# 2_MCU.net
KiCad netlist of a schematic drawn in Altium Designer
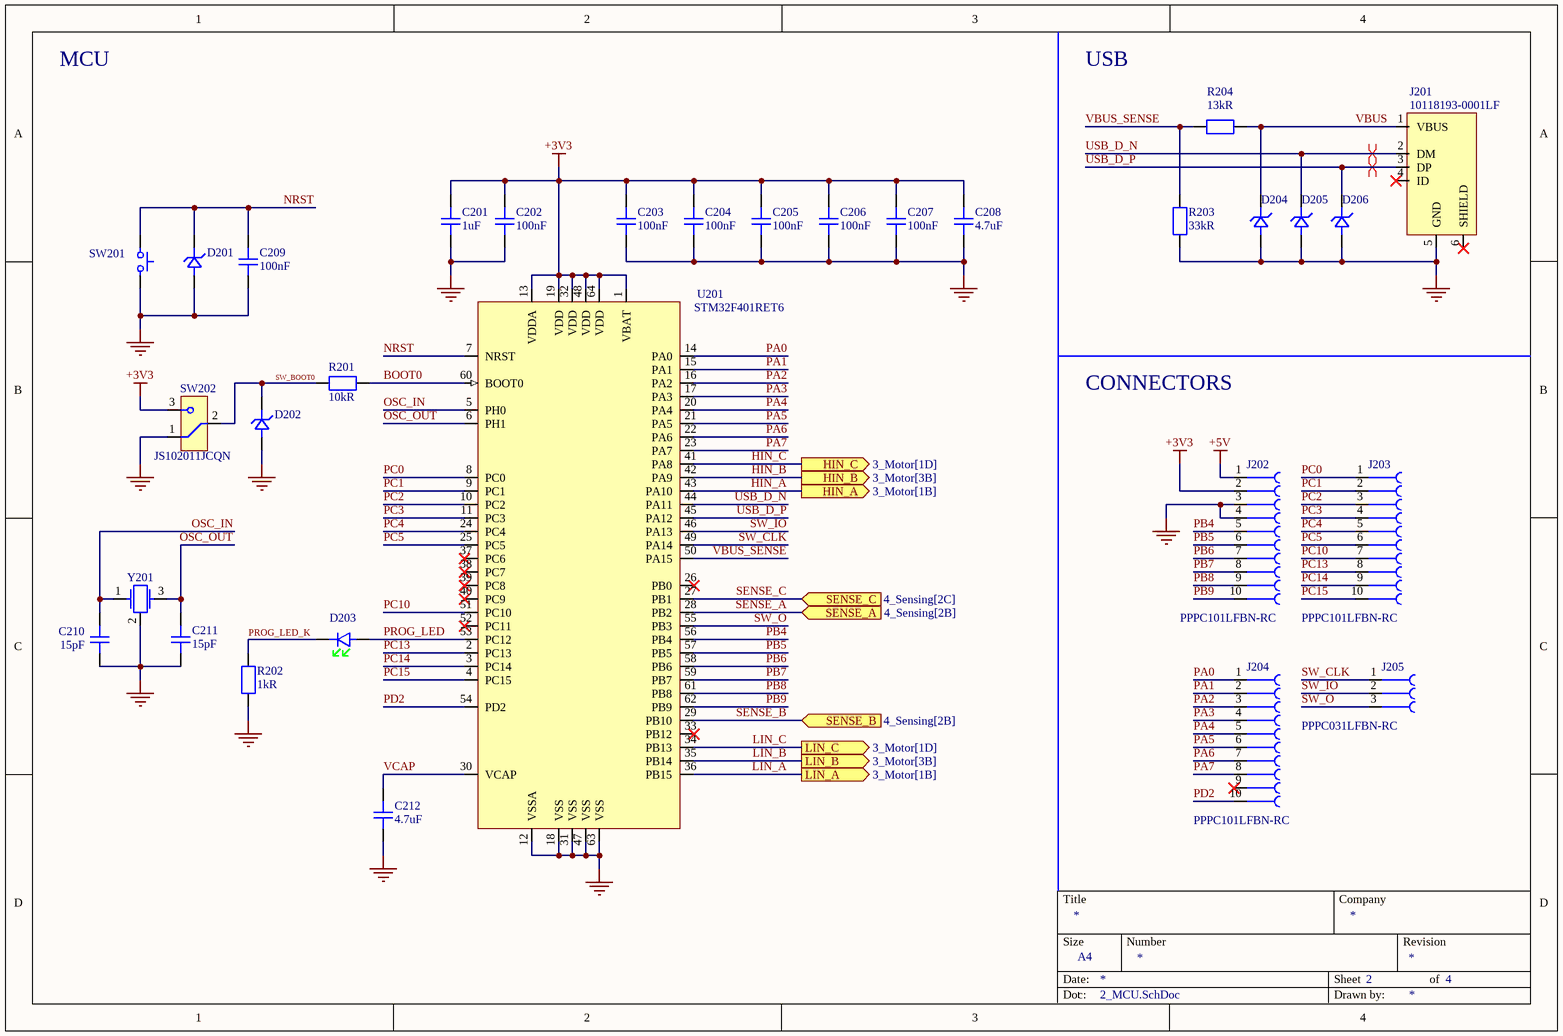
[diagram p0: 2_MCU.SchDoc]

(export (version "E")
  (design (tool "Eeschema 10.0.6"))
  (components
    (comp (ref "C201")
      (value "1uF")
      (footprint "C_Yageo_CC_0603_A")
      (description "Multilayer Ceramic Capacitor, 1 uF, 16 V, ± 10%, X7R, 0603 [1608 Metric]")
      (fields (field (name "TOLERANCE") "10%") (field (name "VOLTAGE") "16V"))
      (libsource (lib "Dennis Micro Computers") (part "C"))
    )
    (comp (ref "C202")
      (value "100nF")
      (footprint "C_Yageo_CC_0402_A")
      (description "Multilayer Ceramic Capacitor, 0.1 uF, 10 V, ± 20%, X7R, 0402 [1005 Metric]")
      (fields (field (name "TOLERANCE") "20%") (field (name "LCSC PART NUMBER") "C2171572"))
      (libsource (lib "Dennis Micro Computers") (part "C"))
    )
    (comp (ref "C203")
      (value "100nF")
      (footprint "C_Yageo_CC_0402_A")
      (description "Multilayer Ceramic Capacitor, 0.1 uF, 10 V, ± 20%, X7R, 0402 [1005 Metric]")
      (fields (field (name "TOLERANCE") "20%") (field (name "LCSC PART NUMBER") "C2171572"))
      (libsource (lib "Dennis Micro Computers") (part "C"))
    )
    (comp (ref "C204")
      (value "100nF")
      (footprint "C_Yageo_CC_0402_A")
      (description "Multilayer Ceramic Capacitor, 0.1 uF, 10 V, ± 20%, X7R, 0402 [1005 Metric]")
      (fields (field (name "TOLERANCE") "20%") (field (name "LCSC PART NUMBER") "C2171572"))
      (libsource (lib "Dennis Micro Computers") (part "C"))
    )
    (comp (ref "C205")
      (value "100nF")
      (footprint "C_Yageo_CC_0402_A")
      (description "Multilayer Ceramic Capacitor, 0.1 uF, 10 V, ± 20%, X7R, 0402 [1005 Metric]")
      (fields (field (name "TOLERANCE") "20%") (field (name "LCSC PART NUMBER") "C2171572"))
      (libsource (lib "Dennis Micro Computers") (part "C"))
    )
    (comp (ref "C206")
      (value "100nF")
      (footprint "C_Yageo_CC_0402_A")
      (description "Multilayer Ceramic Capacitor, 0.1 uF, 10 V, ± 20%, X7R, 0402 [1005 Metric]")
      (fields (field (name "TOLERANCE") "20%") (field (name "LCSC PART NUMBER") "C2171572"))
      (libsource (lib "Dennis Micro Computers") (part "C"))
    )
    (comp (ref "C207")
      (value "100nF")
      (footprint "C_Yageo_CC_0402_A")
      (description "Multilayer Ceramic Capacitor, 0.1 uF, 10 V, ± 20%, X7R, 0402 [1005 Metric]")
      (fields (field (name "TOLERANCE") "20%") (field (name "LCSC PART NUMBER") "C2171572"))
      (libsource (lib "Dennis Micro Computers") (part "C"))
    )
    (comp (ref "C208")
      (value "4.7uF")
      (footprint "C_Yageo_CC_0402_A")
      (description "Multilayer Ceramic Capacitor, 4.7 uF, 50 V, ± 10%, X5R, 0402 [1005 Metric]")
      (fields (field (name "TOLERANCE") "20%") (field (name "LCSC PART NUMBER") "C469468"))
      (libsource (lib "Dennis Micro Computers") (part "C"))
    )
    (comp (ref "C209")
      (value "100nF")
      (footprint "C_Yageo_CC_0402_A")
      (description "Multilayer Ceramic Capacitor, 0.1 uF, 10 V, ± 20%, X7R, 0402 [1005 Metric]")
      (fields (field (name "TOLERANCE") "20%") (field (name "LCSC PART NUMBER") "C2171572"))
      (libsource (lib "Dennis Micro Computers") (part "C"))
    )
    (comp (ref "C210")
      (value "15pF")
      (footprint "C_Yageo_CC_0402_A")
      (description "Multilayer Ceramic Capacitor, 15 pF, 10 V, ± 5%, X7R, 0402 [1005 Metric]")
      (fields (field (name "TOLERANCE") "5%") (field (name "VOLTAGE") "50V"))
      (libsource (lib "Dennis Micro Computers") (part "C"))
    )
    (comp (ref "C211")
      (value "15pF")
      (footprint "C_Yageo_CC_0402_A")
      (description "Multilayer Ceramic Capacitor, 15 pF, 10 V, ± 5%, X7R, 0402 [1005 Metric]")
      (fields (field (name "TOLERANCE") "5%") (field (name "VOLTAGE") "50V"))
      (libsource (lib "Dennis Micro Computers") (part "C"))
    )
    (comp (ref "C212")
      (value "4.7uF")
      (footprint "C_Yageo_CC_0402_A")
      (description "Multilayer Ceramic Capacitor, 4.7 uF, 50 V, ± 10%, X5R, 0402 [1005 Metric]")
      (fields (field (name "TOLERANCE") "20%") (field (name "LCSC PART NUMBER") "C469468"))
      (libsource (lib "Dennis Micro Computers") (part "C"))
    )
    (comp (ref "D201")
      (value "D5V0F1U2S9-7")
      (footprint "D_TVS_Uni_Diodes_SOD-923_B")
      (description "Diode TVS Dual Uni-Dir 5.5V 250000W 2-Pin SOD-923 T/R")
      (fields (field (name "LCSC PART NUMBER") "C508179"))
      (libsource (lib "Dennis Micro Computers") (part "D_TVS_Uni"))
    )
    (comp (ref "D202")
      (value "D5V0F1U2S9-7")
      (footprint "D_TVS_Uni_Diodes_SOD-923_B")
      (description "Diode TVS Dual Uni-Dir 5.5V 250000W 2-Pin SOD-923 T/R")
      (fields (field (name "LCSC PART NUMBER") "C508179"))
      (libsource (lib "Dennis Micro Computers") (part "D_TVS_Uni"))
    )
    (comp (ref "D203")
      (value "150080GS75000")
      (footprint "D_LED_We_150080GS75000")
      (description "WURTH ELEKTRONIK - 150080GS75000 - LED, Green, SMD, 0805, 30 mA, 3.2 V, 520 nm")
      (fields (field (name "LCSC PART NUMBER") "C2890404"))
      (libsource (lib "Dennis Micro Computers") (part "D_LED_Green"))
    )
    (comp (ref "D204")
      (value "D5V0F1U2S9-7")
      (footprint "D_TVS_Uni_Diodes_SOD-923_B")
      (description "Diode TVS Dual Uni-Dir 5.5V 250000W 2-Pin SOD-923 T/R")
      (fields (field (name "LCSC PART NUMBER") "C508179"))
      (libsource (lib "Dennis Micro Computers") (part "D_TVS_Uni"))
    )
    (comp (ref "D205")
      (value "D5V0F1U2S9-7")
      (footprint "D_TVS_Uni_Diodes_SOD-923_B")
      (description "Diode TVS Dual Uni-Dir 5.5V 250000W 2-Pin SOD-923 T/R")
      (fields (field (name "LCSC PART NUMBER") "C508179"))
      (libsource (lib "Dennis Micro Computers") (part "D_TVS_Uni"))
    )
    (comp (ref "D206")
      (value "D5V0F1U2S9-7")
      (footprint "D_TVS_Uni_Diodes_SOD-923_B")
      (description "Diode TVS Dual Uni-Dir 5.5V 250000W 2-Pin SOD-923 T/R")
      (fields (field (name "LCSC PART NUMBER") "C508179"))
      (libsource (lib "Dennis Micro Computers") (part "D_TVS_Uni"))
    )
    (comp (ref "J201")
      (value "10118193-0001LF")
      (footprint "J_USB_Micro-B_Amphenol_10118193-0001LF")
      (description "Usb Connector, 5 Contact(S), Female, Right Angle, Surface Mount Terminal, Locking, Receptacle")
      (fields (field (name "LCSC PART NUMBER") "C132562"))
      (libsource (lib "Dennis Micro Computers") (part "J_USB2_B_Micro"))
    )
    (comp (ref "J202")
      (value "PPPC101LFBN-RC")
      (footprint "J_Sullins_01x07_Socket_2.54mm")
      (description "10 Position Total Single Row 2.54 mm Pitch Straight Female Header")
      (fields (field (name "LCSC PART NUMBER") "Null"))
      (libsource (lib "Dennis Micro Computers") (part "J_01x10_Socket"))
    )
    (comp (ref "J203")
      (value "PPPC101LFBN-RC")
      (footprint "J_Sullins_01x07_Socket_2.54mm")
      (description "10 Position Total Single Row 2.54 mm Pitch Straight Female Header")
      (fields (field (name "LCSC PART NUMBER") "Null"))
      (libsource (lib "Dennis Micro Computers") (part "J_01x10_Socket"))
    )
    (comp (ref "J204")
      (value "PPPC101LFBN-RC")
      (footprint "J_Sullins_01x07_Socket_2.54mm")
      (description "10 Position Total Single Row 2.54 mm Pitch Straight Female Header")
      (fields (field (name "LCSC PART NUMBER") "Null"))
      (libsource (lib "Dennis Micro Computers") (part "J_01x10_Socket"))
    )
    (comp (ref "J205")
      (value "PPPC031LFBN-RC")
      (footprint "J_Sullins_01x03_Socket_2.54mm")
      (description "3 Position Total Single Row 2.54 mm Pitch Straight Female Header")
      (fields (field (name "LCSC PART NUMBER") "Null"))
      (libsource (lib "Dennis Micro Computers") (part "J_01x03_Socket"))
    )
    (comp (ref "R201")
      (value "10kR")
      (footprint "R_Yageo_RCL_0402_A")
      (description "SMD Chip Resistor, 10 kOhm, ± 1%, 62.5 mW, 0402 [1005 Metric], Thick Film, General Purpose")
      (fields (field (name "TOLERANCE") "1%") (field (name "LCSC PART NUMBER") "C60490"))
      (libsource (lib "Dennis Micro Computers") (part "R"))
    )
    (comp (ref "R202")
      (value "1kR")
      (footprint "R_Yageo_RCL_0402_A")
      (description "SMD Chip Resistor, 1 kOhm, ± 1%, 62.5 mW, 0402 [1005 Metric], Thick Film, General Purpose")
      (fields (field (name "TOLERANCE") "1%") (field (name "LCSC PART NUMBER") "C106235"))
      (libsource (lib "Dennis Micro Computers") (part "R"))
    )
    (comp (ref "R203")
      (value "33kR")
      (footprint "R_Yageo_RCL_0402_A")
      (description "SMD Chip Resistor, 33 kOhm, ± 1%, 63 mW, 0402 [1005 Metric], Thick Film, General Purpose")
      (fields (field (name "TOLERANCE") "1%") (field (name "LCSC PART NUMBER") "C138003"))
      (libsource (lib "Dennis Micro Computers") (part "R"))
    )
    (comp (ref "R204")
      (value "13kR")
      (footprint "R_Yageo_RCL_0402_A")
      (description "SMD Chip Resistor, 13 kOhm, ± 1%, 63 mW, 0402 [1005 Metric], Thick Film, General Purpose")
      (fields (field (name "TOLERANCE") "1%") (field (name "LCSC PART NUMBER") "C138057"))
      (libsource (lib "Dennis Micro Computers") (part "R"))
    )
    (comp (ref "SW201")
      (value "PTS647SN50SMTR2LFS")
      (footprint "SW_Tactitle_SPST_C&K_PTS647SN50SMTR2LFS")
      (description "Switch Tactile N.O. SPST Round Button Gull Wing 0.05A 12VDC 100000Cycles 0.98N SMD T/R")
      (fields (field (name "LCSC PART NUMBER") "C2799414"))
      (libsource (lib "Dennis Micro Computers") (part "SW_Tactile_SPST"))
    )
    (comp (ref "SW202")
      (value "JS102011JCQN")
      (footprint "SW_Slide_C&K_JS102011JCQN")
      (description "JS Series Sub-Miniature Slide Switch SPDT On-On Top Slide 0.3A 6VDC J-Lead Surface Mount T/R")
      (fields (field (name "LCSC PART NUMBER") "C221659"))
      (libsource (lib "Dennis Micro Computers") (part "SW_Slide_SPDT"))
    )
    (comp (ref "U201")
      (value "STM32F401RET6")
      (footprint "U_ST_STM32F401xD/xE_B")
      (description "MCU 32-bit STM32 ARM Cortex M4 RISC 512KB Flash 1.8V/2.5V/3.3V 64-Pin LQFP Tray")
      (fields (field (name "LCSC PART NUMBER") "C116978"))
      (libsource (lib "Dennis Micro Computers") (part "U_STM32F401xD/xE"))
    )
    (comp (ref "Y201")
      (value "ECS-240-12-37B-CKY-TR")
      (footprint "Y_Crystal_GND24_ECS_240-12-37B-CKY-TR")
      (description "Crystal 24MHz ±10ppm (Tol) ±10ppm (Stability) 12pF FUND 50Ohm 4-Pin Mini-CSMD T/R")
      (fields (field (name "LCSC PART NUMBER") "C2450025"))
      (libsource (lib "Dennis Micro Computers") (part "Y_Crystal_GND24"))
    )
  )
  (nets
    (net (code "1") (name "+3V3") (class "Default")
      (node (ref "C201") (pin "2") (pinfunction "2_2") (pintype "passive"))
      (node (ref "C202") (pin "2") (pinfunction "2_2") (pintype "passive"))
      (node (ref "C203") (pin "2") (pinfunction "2_2") (pintype "passive"))
      (node (ref "C204") (pin "2") (pinfunction "2_2") (pintype "passive"))
      (node (ref "C205") (pin "2") (pinfunction "2_2") (pintype "passive"))
      (node (ref "C206") (pin "2") (pinfunction "2_2") (pintype "passive"))
      (node (ref "C207") (pin "2") (pinfunction "2_2") (pintype "passive"))
      (node (ref "C208") (pin "2") (pinfunction "2_2") (pintype "passive"))
      (node (ref "J202") (pin "2") (pinfunction "2_2") (pintype "passive"))
      (node (ref "SW202") (pin "3") (pinfunction "3_3") (pintype "passive"))
      (node (ref "U201") (pin "1") (pinfunction "VBAT_1") (pintype "power_in"))
      (node (ref "U201") (pin "13") (pinfunction "VDDA_13") (pintype "power_in"))
      (node (ref "U201") (pin "19") (pinfunction "VDD_19") (pintype "power_in"))
      (node (ref "U201") (pin "32") (pinfunction "VDD_32") (pintype "power_in"))
      (node (ref "U201") (pin "48") (pinfunction "VDD_48") (pintype "power_in"))
      (node (ref "U201") (pin "64") (pinfunction "VDD_64") (pintype "power_in"))
    )
    (net (code "2") (name "+5V") (class "Default")
      (node (ref "J202") (pin "1") (pinfunction "1_1") (pintype "passive"))
    )
    (net (code "3") (name "/BOOT0") (class "Default")
      (node (ref "R201") (pin "2") (pinfunction "2_2") (pintype "passive"))
      (node (ref "U201") (pin "60") (pinfunction "BOOT0_60") (pintype "input"))
    )
    (net (code "4") (name "/HIN_A") (class "Default")
      (node (ref "U201") (pin "43") (pinfunction "PA10_43") (pintype "bidirectional"))
    )
    (net (code "5") (name "/HIN_B") (class "Default")
      (node (ref "U201") (pin "42") (pinfunction "PA9_42") (pintype "bidirectional"))
    )
    (net (code "6") (name "/HIN_C") (class "Default")
      (node (ref "U201") (pin "41") (pinfunction "PA8_41") (pintype "bidirectional"))
    )
    (net (code "7") (name "/LIN_A") (class "Default")
      (node (ref "U201") (pin "36") (pinfunction "PB15_36") (pintype "bidirectional"))
    )
    (net (code "8") (name "/LIN_B") (class "Default")
      (node (ref "U201") (pin "35") (pinfunction "PB14_35") (pintype "bidirectional"))
    )
    (net (code "9") (name "/LIN_C") (class "Default")
      (node (ref "U201") (pin "34") (pinfunction "PB13_34") (pintype "bidirectional"))
    )
    (net (code "10") (name "/NRST") (class "Default")
      (node (ref "C209") (pin "2") (pinfunction "2_2") (pintype "passive"))
      (node (ref "D201") (pin "1") (pinfunction "1_1") (pintype "passive"))
      (node (ref "SW201") (pin "1") (pinfunction "1_1") (pintype "passive"))
      (node (ref "U201") (pin "7") (pinfunction "NRST_7") (pintype "bidirectional"))
    )
    (net (code "11") (name "/OSC_IN") (class "Default")
      (node (ref "C210") (pin "2") (pinfunction "2_2") (pintype "passive"))
      (node (ref "U201") (pin "5") (pinfunction "PH0_5") (pintype "bidirectional"))
      (node (ref "Y201") (pin "1") (pinfunction "1_1") (pintype "passive"))
    )
    (net (code "12") (name "/OSC_OUT") (class "Default")
      (node (ref "C211") (pin "2") (pinfunction "2_2") (pintype "passive"))
      (node (ref "U201") (pin "6") (pinfunction "PH1_6") (pintype "bidirectional"))
      (node (ref "Y201") (pin "3") (pinfunction "3_3") (pintype "passive"))
    )
    (net (code "13") (name "/PA0") (class "Default")
      (node (ref "J204") (pin "1") (pinfunction "1_1") (pintype "passive"))
      (node (ref "U201") (pin "14") (pinfunction "PA0_14") (pintype "bidirectional"))
    )
    (net (code "14") (name "/PA1") (class "Default")
      (node (ref "J204") (pin "2") (pinfunction "2_2") (pintype "passive"))
      (node (ref "U201") (pin "15") (pinfunction "PA1_15") (pintype "bidirectional"))
    )
    (net (code "15") (name "/PA2") (class "Default")
      (node (ref "J204") (pin "3") (pinfunction "3_3") (pintype "passive"))
      (node (ref "U201") (pin "16") (pinfunction "PA2_16") (pintype "bidirectional"))
    )
    (net (code "16") (name "/PA3") (class "Default")
      (node (ref "J204") (pin "4") (pinfunction "4_4") (pintype "passive"))
      (node (ref "U201") (pin "17") (pinfunction "PA3_17") (pintype "bidirectional"))
    )
    (net (code "17") (name "/PA4") (class "Default")
      (node (ref "J204") (pin "5") (pinfunction "5_5") (pintype "passive"))
      (node (ref "U201") (pin "20") (pinfunction "PA4_20") (pintype "bidirectional"))
    )
    (net (code "18") (name "/PA5") (class "Default")
      (node (ref "J204") (pin "6") (pinfunction "6_6") (pintype "passive"))
      (node (ref "U201") (pin "21") (pinfunction "PA5_21") (pintype "bidirectional"))
    )
    (net (code "19") (name "/PA6") (class "Default")
      (node (ref "J204") (pin "7") (pinfunction "7_7") (pintype "passive"))
      (node (ref "U201") (pin "22") (pinfunction "PA6_22") (pintype "bidirectional"))
    )
    (net (code "20") (name "/PA7") (class "Default")
      (node (ref "J204") (pin "8") (pinfunction "8_8") (pintype "passive"))
      (node (ref "U201") (pin "23") (pinfunction "PA7_23") (pintype "bidirectional"))
    )
    (net (code "21") (name "/PB4") (class "Default")
      (node (ref "J202") (pin "5") (pinfunction "5_5") (pintype "passive"))
      (node (ref "U201") (pin "56") (pinfunction "PB4_56") (pintype "bidirectional"))
    )
    (net (code "22") (name "/PB5") (class "Default")
      (node (ref "J202") (pin "6") (pinfunction "6_6") (pintype "passive"))
      (node (ref "U201") (pin "57") (pinfunction "PB5_57") (pintype "bidirectional"))
    )
    (net (code "23") (name "/PB6") (class "Default")
      (node (ref "J202") (pin "7") (pinfunction "7_7") (pintype "passive"))
      (node (ref "U201") (pin "58") (pinfunction "PB6_58") (pintype "bidirectional"))
    )
    (net (code "24") (name "/PB7") (class "Default")
      (node (ref "J202") (pin "8") (pinfunction "8_8") (pintype "passive"))
      (node (ref "U201") (pin "59") (pinfunction "PB7_59") (pintype "bidirectional"))
    )
    (net (code "25") (name "/PB8") (class "Default")
      (node (ref "J202") (pin "9") (pinfunction "9_9") (pintype "passive"))
      (node (ref "U201") (pin "61") (pinfunction "PB8_61") (pintype "bidirectional"))
    )
    (net (code "26") (name "/PB9") (class "Default")
      (node (ref "J202") (pin "10") (pinfunction "10_10") (pintype "passive"))
      (node (ref "U201") (pin "62") (pinfunction "PB9_62") (pintype "bidirectional"))
    )
    (net (code "27") (name "/PC0") (class "Default")
      (node (ref "J203") (pin "1") (pinfunction "1_1") (pintype "passive"))
      (node (ref "U201") (pin "8") (pinfunction "PC0_8") (pintype "bidirectional"))
    )
    (net (code "28") (name "/PC1") (class "Default")
      (node (ref "J203") (pin "2") (pinfunction "2_2") (pintype "passive"))
      (node (ref "U201") (pin "9") (pinfunction "PC1_9") (pintype "bidirectional"))
    )
    (net (code "29") (name "/PC2") (class "Default")
      (node (ref "J203") (pin "3") (pinfunction "3_3") (pintype "passive"))
      (node (ref "U201") (pin "10") (pinfunction "PC2_10") (pintype "bidirectional"))
    )
    (net (code "30") (name "/PC3") (class "Default")
      (node (ref "J203") (pin "4") (pinfunction "4_4") (pintype "passive"))
      (node (ref "U201") (pin "11") (pinfunction "PC3_11") (pintype "bidirectional"))
    )
    (net (code "31") (name "/PC4") (class "Default")
      (node (ref "J203") (pin "5") (pinfunction "5_5") (pintype "passive"))
      (node (ref "U201") (pin "24") (pinfunction "PC4_24") (pintype "bidirectional"))
    )
    (net (code "32") (name "/PC5") (class "Default")
      (node (ref "J203") (pin "6") (pinfunction "6_6") (pintype "passive"))
      (node (ref "U201") (pin "25") (pinfunction "PC5_25") (pintype "bidirectional"))
    )
    (net (code "33") (name "/PC10") (class "Default")
      (node (ref "J203") (pin "7") (pinfunction "7_7") (pintype "passive"))
      (node (ref "U201") (pin "51") (pinfunction "PC10_51") (pintype "bidirectional"))
    )
    (net (code "34") (name "/PC13") (class "Default")
      (node (ref "J203") (pin "8") (pinfunction "8_8") (pintype "passive"))
      (node (ref "U201") (pin "2") (pinfunction "PC13_2") (pintype "bidirectional"))
    )
    (net (code "35") (name "/PC14") (class "Default")
      (node (ref "J203") (pin "9") (pinfunction "9_9") (pintype "passive"))
      (node (ref "U201") (pin "3") (pinfunction "PC14_3") (pintype "bidirectional"))
    )
    (net (code "36") (name "/PC15") (class "Default")
      (node (ref "J203") (pin "10") (pinfunction "10_10") (pintype "passive"))
      (node (ref "U201") (pin "4") (pinfunction "PC15_4") (pintype "bidirectional"))
    )
    (net (code "37") (name "/PD2") (class "Default")
      (node (ref "J204") (pin "10") (pinfunction "10_10") (pintype "passive"))
      (node (ref "U201") (pin "54") (pinfunction "PD2_54") (pintype "bidirectional"))
    )
    (net (code "38") (name "/PROG_LED") (class "Default")
      (node (ref "D203") (pin "1") (pinfunction "1_1") (pintype "passive"))
      (node (ref "U201") (pin "53") (pinfunction "PC12_53") (pintype "bidirectional"))
    )
    (net (code "39") (name "/PROG_LED_K") (class "Default")
      (node (ref "D203") (pin "2") (pinfunction "2_2") (pintype "passive"))
      (node (ref "R202") (pin "2") (pinfunction "2_2") (pintype "passive"))
    )
    (net (code "40") (name "/SENSE_A") (class "Default")
      (node (ref "U201") (pin "28") (pinfunction "PB2_28") (pintype "bidirectional"))
    )
    (net (code "41") (name "/SENSE_B") (class "Default")
      (node (ref "U201") (pin "29") (pinfunction "PB10_29") (pintype "bidirectional"))
    )
    (net (code "42") (name "/SENSE_C") (class "Default")
      (node (ref "U201") (pin "27") (pinfunction "PB1_27") (pintype "bidirectional"))
    )
    (net (code "43") (name "/SW_BOOT0") (class "Default")
      (node (ref "D202") (pin "1") (pinfunction "1_1") (pintype "passive"))
      (node (ref "R201") (pin "1") (pinfunction "1_1") (pintype "passive"))
      (node (ref "SW202") (pin "2") (pinfunction "2_2") (pintype "passive"))
    )
    (net (code "44") (name "/SW_CLK") (class "Default")
      (node (ref "J205") (pin "1") (pinfunction "1_1") (pintype "passive"))
      (node (ref "U201") (pin "49") (pinfunction "PA14_49") (pintype "bidirectional"))
    )
    (net (code "45") (name "/SW_IO") (class "Default")
      (node (ref "J205") (pin "2") (pinfunction "2_2") (pintype "passive"))
      (node (ref "U201") (pin "46") (pinfunction "PA13_46") (pintype "bidirectional"))
    )
    (net (code "46") (name "/SW_O") (class "Default")
      (node (ref "J205") (pin "3") (pinfunction "3_3") (pintype "passive"))
      (node (ref "U201") (pin "55") (pinfunction "PB3_55") (pintype "bidirectional"))
    )
    (net (code "47") (name "/USB_D_N") (class "Default")
      (node (ref "D205") (pin "1") (pinfunction "1_1") (pintype "passive"))
      (node (ref "J201") (pin "2") (pinfunction "DM_2") (pintype "bidirectional"))
      (node (ref "U201") (pin "44") (pinfunction "PA11_44") (pintype "bidirectional"))
    )
    (net (code "48") (name "/USB_D_P") (class "Default")
      (node (ref "D206") (pin "1") (pinfunction "1_1") (pintype "passive"))
      (node (ref "J201") (pin "3") (pinfunction "DP_3") (pintype "bidirectional"))
      (node (ref "U201") (pin "45") (pinfunction "PA12_45") (pintype "bidirectional"))
    )
    (net (code "49") (name "/VBUS") (class "Default")
      (node (ref "D204") (pin "1") (pinfunction "1_1") (pintype "passive"))
      (node (ref "J201") (pin "1") (pinfunction "VBUS_1") (pintype "power_in"))
      (node (ref "R204") (pin "2") (pinfunction "2_2") (pintype "passive"))
    )
    (net (code "50") (name "/VBUS_SENSE") (class "Default")
      (node (ref "R203") (pin "2") (pinfunction "2_2") (pintype "passive"))
      (node (ref "R204") (pin "1") (pinfunction "1_1") (pintype "passive"))
      (node (ref "U201") (pin "50") (pinfunction "PA15_50") (pintype "bidirectional"))
    )
    (net (code "51") (name "/VCAP") (class "Default")
      (node (ref "C212") (pin "2") (pinfunction "2_2") (pintype "passive"))
      (node (ref "U201") (pin "30") (pinfunction "VCAP_30") (pintype "power_in"))
    )
    (net (code "52") (name "GND") (class "Default")
      (node (ref "C201") (pin "1") (pinfunction "1_1") (pintype "passive"))
      (node (ref "C202") (pin "1") (pinfunction "1_1") (pintype "passive"))
      (node (ref "C203") (pin "1") (pinfunction "1_1") (pintype "passive"))
      (node (ref "C204") (pin "1") (pinfunction "1_1") (pintype "passive"))
      (node (ref "C205") (pin "1") (pinfunction "1_1") (pintype "passive"))
      (node (ref "C206") (pin "1") (pinfunction "1_1") (pintype "passive"))
      (node (ref "C207") (pin "1") (pinfunction "1_1") (pintype "passive"))
      (node (ref "C208") (pin "1") (pinfunction "1_1") (pintype "passive"))
      (node (ref "C209") (pin "1") (pinfunction "1_1") (pintype "passive"))
      (node (ref "C210") (pin "1") (pinfunction "1_1") (pintype "passive"))
      (node (ref "C211") (pin "1") (pinfunction "1_1") (pintype "passive"))
      (node (ref "C212") (pin "1") (pinfunction "1_1") (pintype "passive"))
      (node (ref "D201") (pin "2") (pinfunction "2_2") (pintype "passive"))
      (node (ref "D202") (pin "2") (pinfunction "2_2") (pintype "passive"))
      (node (ref "D204") (pin "2") (pinfunction "2_2") (pintype "passive"))
      (node (ref "D205") (pin "2") (pinfunction "2_2") (pintype "passive"))
      (node (ref "D206") (pin "2") (pinfunction "2_2") (pintype "passive"))
      (node (ref "J201") (pin "5") (pinfunction "GND_5") (pintype "power_in"))
      (node (ref "J202") (pin "3") (pinfunction "3_3") (pintype "passive"))
      (node (ref "J202") (pin "4") (pinfunction "4_4") (pintype "passive"))
      (node (ref "R202") (pin "1") (pinfunction "1_1") (pintype "passive"))
      (node (ref "R203") (pin "1") (pinfunction "1_1") (pintype "passive"))
      (node (ref "SW201") (pin "2") (pinfunction "2_2") (pintype "passive"))
      (node (ref "SW202") (pin "1") (pinfunction "1_1") (pintype "passive"))
      (node (ref "U201") (pin "12") (pinfunction "VSSA_12") (pintype "power_in"))
      (node (ref "U201") (pin "18") (pinfunction "VSS_18") (pintype "power_in"))
      (node (ref "U201") (pin "31") (pinfunction "VSS_31") (pintype "power_in"))
      (node (ref "U201") (pin "47") (pinfunction "VSS_47") (pintype "power_in"))
      (node (ref "U201") (pin "63") (pinfunction "VSS_63") (pintype "power_in"))
      (node (ref "Y201") (pin "2") (pinfunction "2_2") (pintype "passive"))
    )
    (net (code "53") (name "unconnected-(J201-ID-Pad4)") (class "Default")
      (node (ref "J201") (pin "4") (pinfunction "ID_4") (pintype "passive+no_connect"))
    )
    (net (code "54") (name "unconnected-(J201-SHIELD-Pad6)") (class "Default")
      (node (ref "J201") (pin "6") (pinfunction "SHIELD_6") (pintype "passive+no_connect"))
    )
    (net (code "55") (name "unconnected-(J204-Pad9)") (class "Default")
      (node (ref "J204") (pin "9") (pinfunction "9_9") (pintype "passive+no_connect"))
    )
    (net (code "56") (name "unconnected-(U201-PB0-Pad26)") (class "Default")
      (node (ref "U201") (pin "26") (pinfunction "PB0_26") (pintype "bidirectional+no_connect"))
    )
    (net (code "57") (name "unconnected-(U201-PB12-Pad33)") (class "Default")
      (node (ref "U201") (pin "33") (pinfunction "PB12_33") (pintype "bidirectional+no_connect"))
    )
    (net (code "58") (name "unconnected-(U201-PC6-Pad37)") (class "Default")
      (node (ref "U201") (pin "37") (pinfunction "PC6_37") (pintype "bidirectional+no_connect"))
    )
    (net (code "59") (name "unconnected-(U201-PC7-Pad38)") (class "Default")
      (node (ref "U201") (pin "38") (pinfunction "PC7_38") (pintype "bidirectional+no_connect"))
    )
    (net (code "60") (name "unconnected-(U201-PC8-Pad39)") (class "Default")
      (node (ref "U201") (pin "39") (pinfunction "PC8_39") (pintype "bidirectional+no_connect"))
    )
    (net (code "61") (name "unconnected-(U201-PC9-Pad40)") (class "Default")
      (node (ref "U201") (pin "40") (pinfunction "PC9_40") (pintype "bidirectional+no_connect"))
    )
    (net (code "62") (name "unconnected-(U201-PC11-Pad52)") (class "Default")
      (node (ref "U201") (pin "52") (pinfunction "PC11_52") (pintype "bidirectional+no_connect"))
    )
  )
)
